# TMP006_Breakout.net
KiCad netlist of a schematic drawn in EAGLE
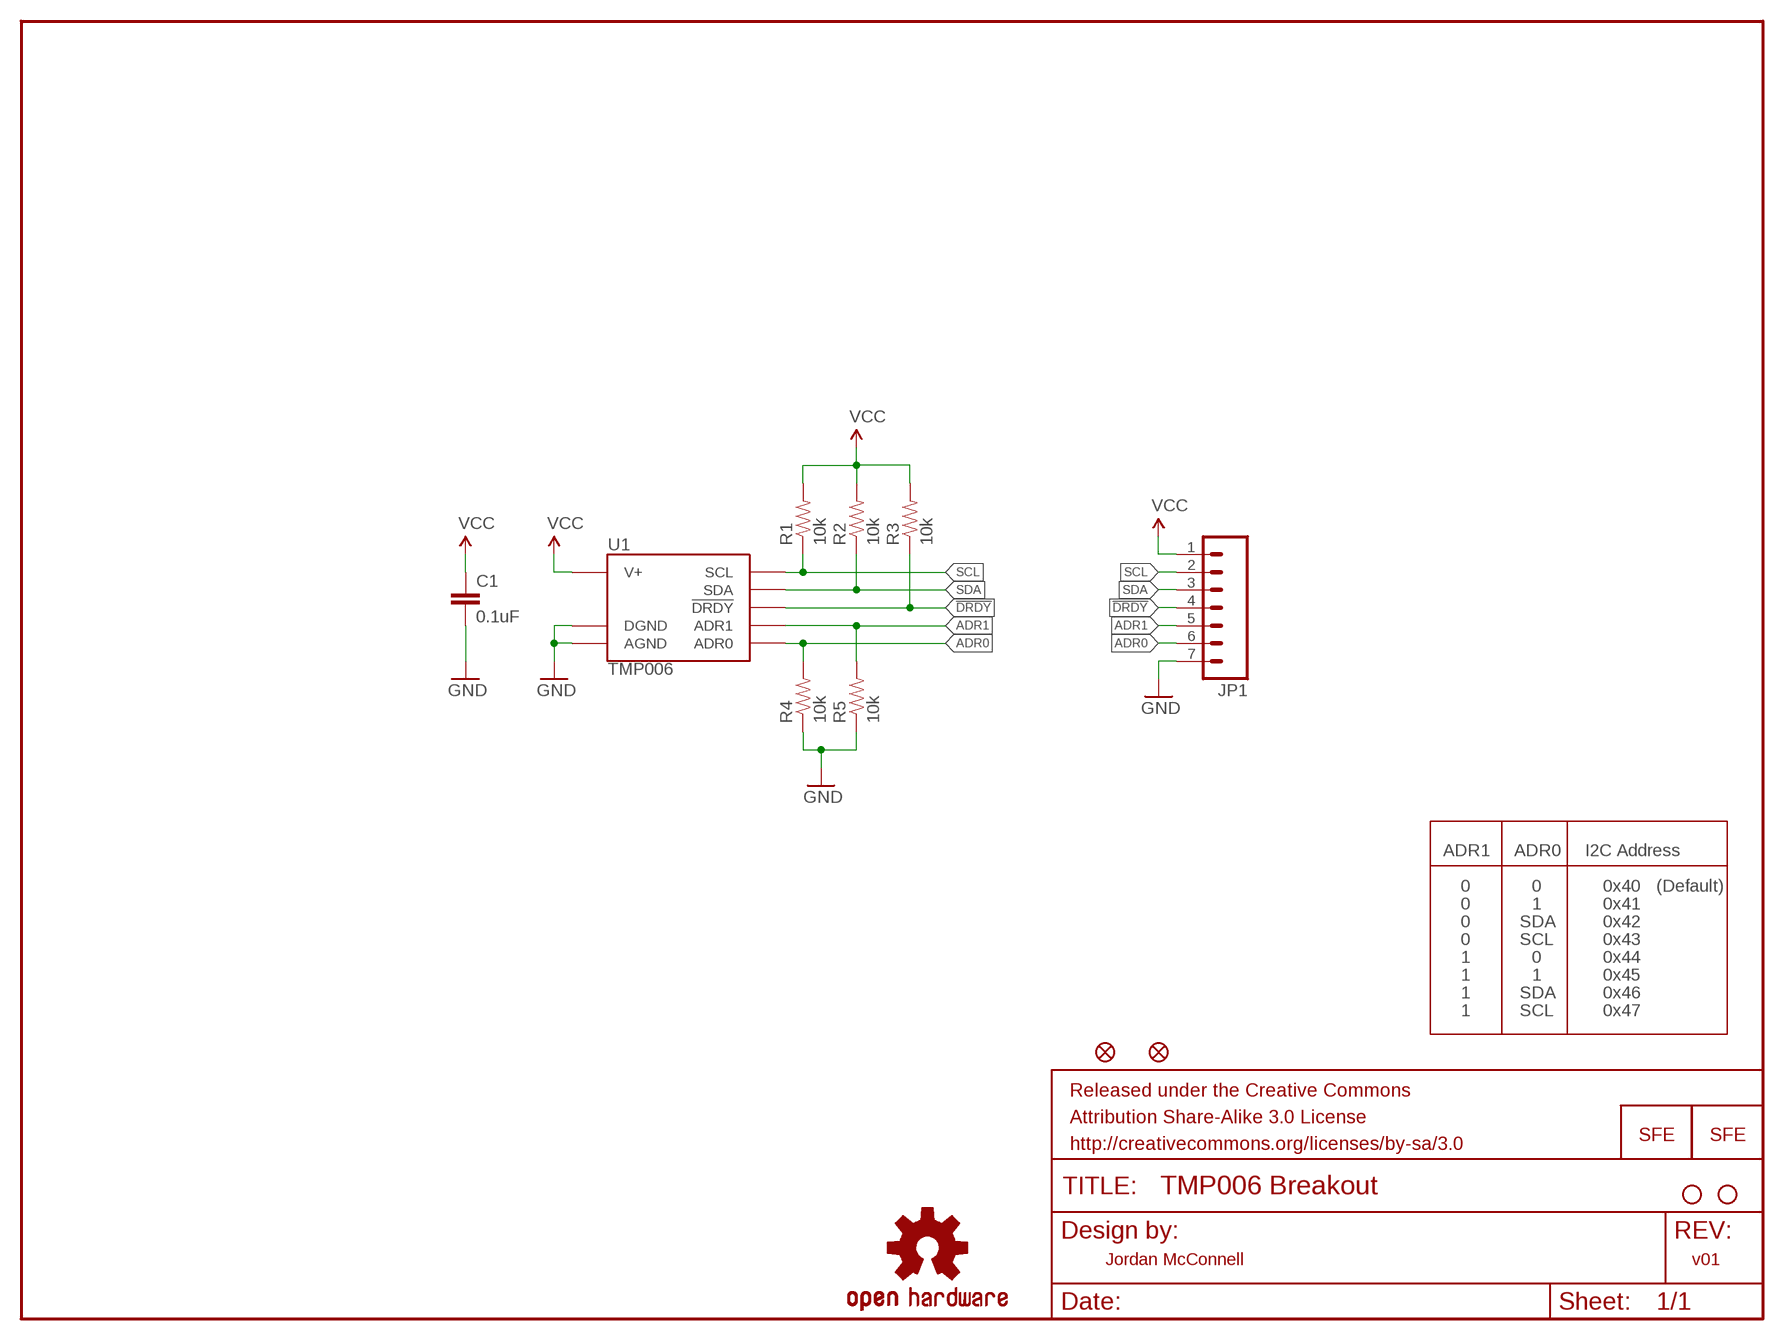
[diagram p0: schematic, sheet 1]

(export (version "E")
  (design (tool "Eeschema 10.0.6"))
  (components
    (comp (ref "C1")
      (value "0.1uF")
      (footprint "eagle-import:0603-CAP")
      (libsource (lib "eagle-import") (part "CAP0603-CAP"))
    )
    (comp (ref "FID1")
      (value "FIDUCIALUFIDUCIAL")
      (footprint "eagle-import:MICRO-FIDUCIAL")
      (libsource (lib "eagle-import") (part "FIDUCIALUFIDUCIAL"))
    )
    (comp (ref "FID2")
      (value "FIDUCIALUFIDUCIAL")
      (footprint "eagle-import:MICRO-FIDUCIAL")
      (libsource (lib "eagle-import") (part "FIDUCIALUFIDUCIAL"))
    )
    (comp (ref "FRAME1")
      (value "FRAME-LETTER")
      (footprint "eagle-import:CREATIVE_COMMONS")
      (libsource (lib "eagle-import") (part "FRAME-LETTER"))
    )
    (comp (ref "JP1")
      (value "M07")
      (footprint "eagle-import:1X07")
      (libsource (lib "eagle-import") (part "M07"))
    )
    (comp (ref "LOGO1")
      (value "LOGO-SFESK")
      (footprint "eagle-import:SFE-LOGO-FLAME")
      (libsource (lib "eagle-import") (part "LOGO-SFESK"))
    )
    (comp (ref "LOGO2")
      (value "OSHW-LOGOS")
      (footprint "eagle-import:OSHW-LOGO-S")
      (libsource (lib "eagle-import") (part "OSHW-LOGOS"))
    )
    (comp (ref "LOGO3")
      (value "LOGO-SFENEW")
      (footprint "eagle-import:SFE-NEW-WEBLOGO")
      (libsource (lib "eagle-import") (part "LOGO-SFENEW"))
    )
    (comp (ref "R1")
      (value "10k")
      (footprint "eagle-import:0603-RES")
      (libsource (lib "eagle-import") (part "RESISTOR0603-RES"))
    )
    (comp (ref "R2")
      (value "10k")
      (footprint "eagle-import:0603-RES")
      (libsource (lib "eagle-import") (part "RESISTOR0603-RES"))
    )
    (comp (ref "R3")
      (value "10k")
      (footprint "eagle-import:0603-RES")
      (libsource (lib "eagle-import") (part "RESISTOR0603-RES"))
    )
    (comp (ref "R4")
      (value "10k")
      (footprint "eagle-import:0603-RES")
      (libsource (lib "eagle-import") (part "RESISTOR0603-RES"))
    )
    (comp (ref "R5")
      (value "10k")
      (footprint "eagle-import:0603-RES")
      (libsource (lib "eagle-import") (part "RESISTOR0603-RES"))
    )
    (comp (ref "STANDOFF1")
      (value "STAND-OFF")
      (footprint "eagle-import:STAND-OFF")
      (libsource (lib "eagle-import") (part "STAND-OFF"))
    )
    (comp (ref "STANDOFF2")
      (value "STAND-OFF")
      (footprint "eagle-import:STAND-OFF")
      (libsource (lib "eagle-import") (part "STAND-OFF"))
    )
    (comp (ref "U1")
      (value "TMP006")
      (footprint "eagle-import:BGA8DS")
      (libsource (lib "eagle-import") (part "TMP006"))
    )
  )
  (nets
    (net (code "1") (name "/~{DRDY}") (class "Default")
      (node (ref "JP1") (pin "4") (pinfunction "4_4") (pintype "passive"))
      (node (ref "R3") (pin "1") (pinfunction "1_1") (pintype "passive"))
      (node (ref "U1") (pin "C2") (pinfunction "~{DRDY}_C2") (pintype "bidirectional"))
    )
    (net (code "2") (name "ADR0") (class "Default")
      (node (ref "JP1") (pin "6") (pinfunction "6_6") (pintype "passive"))
      (node (ref "R4") (pin "2") (pinfunction "2_2") (pintype "passive"))
      (node (ref "U1") (pin "C1") (pinfunction "ADR0_C1") (pintype "bidirectional"))
    )
    (net (code "3") (name "ADR1") (class "Default")
      (node (ref "JP1") (pin "5") (pinfunction "5_5") (pintype "passive"))
      (node (ref "R5") (pin "2") (pinfunction "2_2") (pintype "passive"))
      (node (ref "U1") (pin "B1") (pinfunction "ADR1_B1") (pintype "bidirectional"))
    )
    (net (code "4") (name "GND") (class "Default")
      (node (ref "C1") (pin "2") (pinfunction "2_2") (pintype "passive"))
      (node (ref "JP1") (pin "7") (pinfunction "7_7") (pintype "passive"))
      (node (ref "R4") (pin "1") (pinfunction "1_1") (pintype "passive"))
      (node (ref "R5") (pin "1") (pinfunction "1_1") (pintype "passive"))
      (node (ref "U1") (pin "A1") (pinfunction "DGND_A1") (pintype "bidirectional"))
      (node (ref "U1") (pin "A2") (pinfunction "AGND_A2") (pintype "bidirectional"))
    )
    (net (code "5") (name "SCL") (class "Default")
      (node (ref "JP1") (pin "2") (pinfunction "2_2") (pintype "passive"))
      (node (ref "R1") (pin "1") (pinfunction "1_1") (pintype "passive"))
      (node (ref "U1") (pin "B3") (pinfunction "SCL_B3") (pintype "bidirectional"))
    )
    (net (code "6") (name "SDA") (class "Default")
      (node (ref "JP1") (pin "3") (pinfunction "3_3") (pintype "passive"))
      (node (ref "R2") (pin "1") (pinfunction "1_1") (pintype "passive"))
      (node (ref "U1") (pin "C3") (pinfunction "SDA_C3") (pintype "bidirectional"))
    )
    (net (code "7") (name "VCC") (class "Default")
      (node (ref "C1") (pin "1") (pinfunction "1_1") (pintype "passive"))
      (node (ref "JP1") (pin "1") (pinfunction "1_1") (pintype "passive"))
      (node (ref "R1") (pin "2") (pinfunction "2_2") (pintype "passive"))
      (node (ref "R2") (pin "2") (pinfunction "2_2") (pintype "passive"))
      (node (ref "R3") (pin "2") (pinfunction "2_2") (pintype "passive"))
      (node (ref "U1") (pin "A3") (pinfunction "V+_A3") (pintype "bidirectional"))
    )
  )
)
